# Clock_WR.net
KiCad netlist of a schematic drawn in Altium Designer
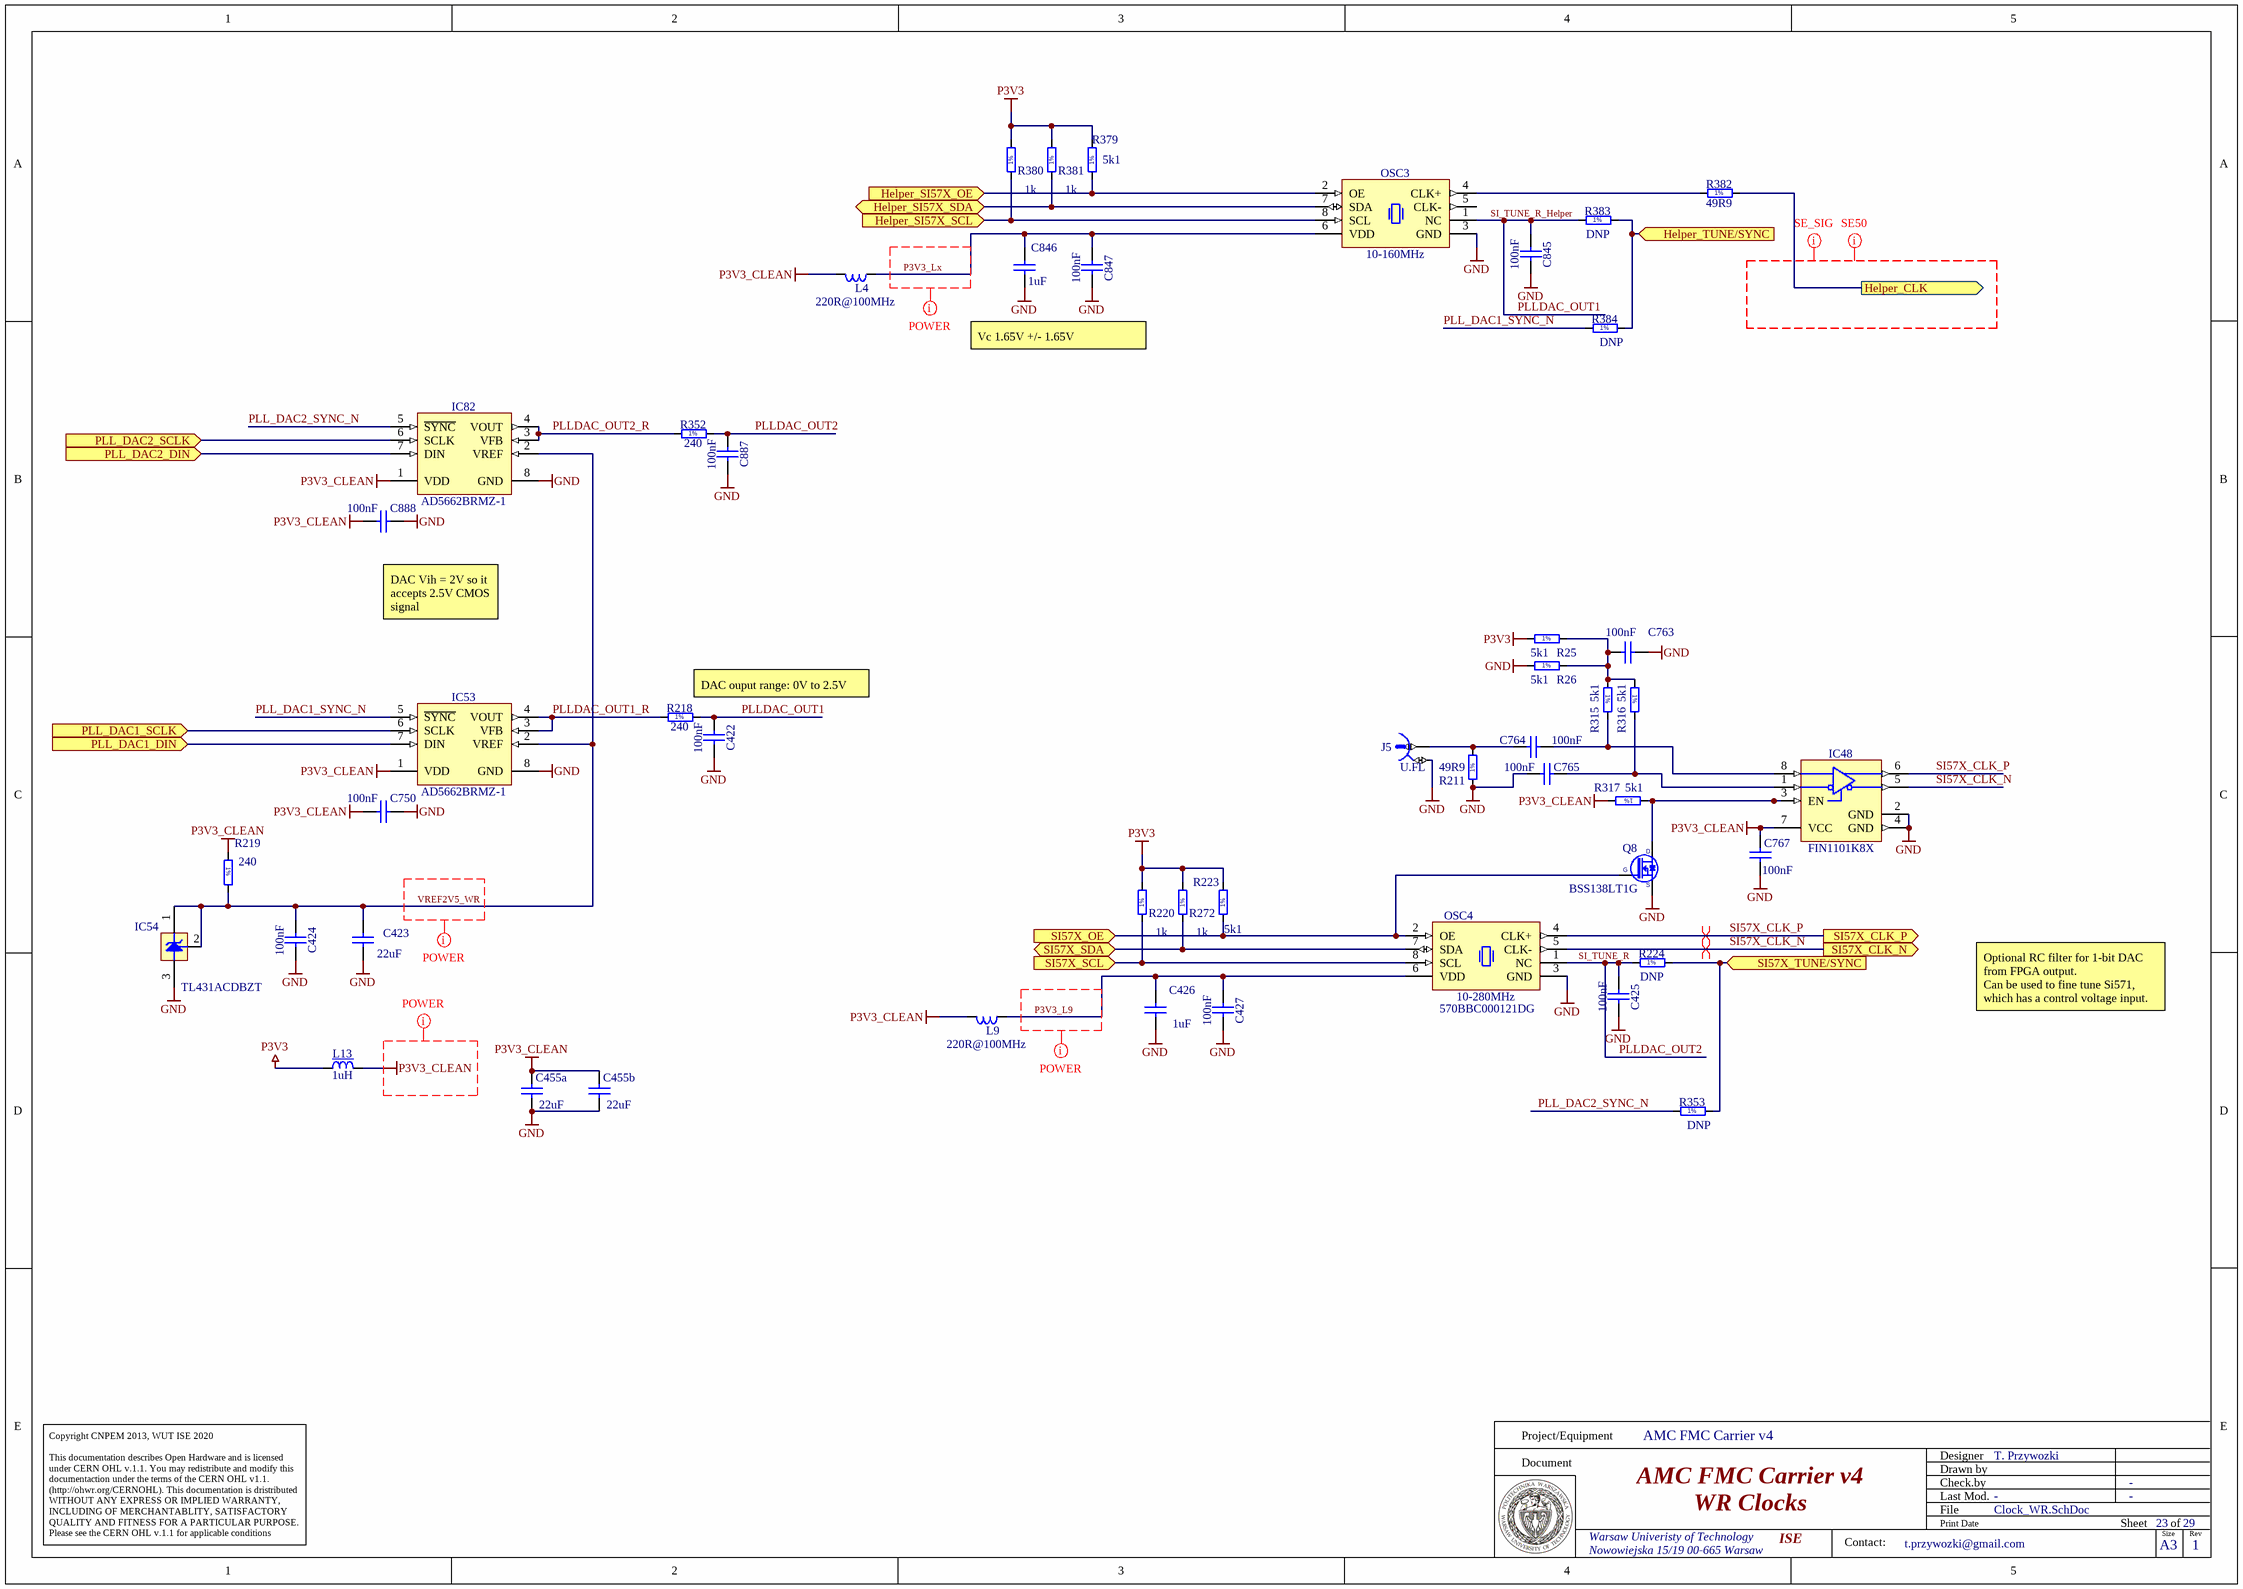
[diagram p0: Clock_WR.SchDoc]

(export (version "E")
  (design (tool "Eeschema 10.0.6"))
  (components
    (comp (ref "C422")
      (value "100nF")
      (footprint "CAPC0603X33N")
      (description "Non-polarised capacitor")
      (fields
        (field (name "PART NUMBER") "CC0201_100NF_6.3V_10%_X5R")
        (field (name "VOLTAGE") "6.3V")
        (field (name "AUTHOR") "CERN DEM JLC")
      )
      (libsource (lib "Capacitors") (part "Capacitor - non polarized"))
    )
    (comp (ref "C423")
      (value "22uF")
      (footprint "CAPC3216X180N")
      (description "Non-polarised capacitor")
      (fields
        (field (name "PART NUMBER") "CC1206_22UF_10V_10%_X7R")
        (field (name "VOLTAGE") "10V")
        (field (name "AUTHOR") "CERN DEM JLC")
      )
      (libsource (lib "Capacitors") (part "Capacitor - non polarized"))
    )
    (comp (ref "C424")
      (value "100nF")
      (footprint "CAPC0603X33N")
      (description "Non-polarised capacitor")
      (fields
        (field (name "PART NUMBER") "CC0201_100NF_6.3V_10%_X5R")
        (field (name "VOLTAGE") "6.3V")
        (field (name "AUTHOR") "CERN DEM JLC")
      )
      (libsource (lib "Capacitors") (part "Capacitor - non polarized"))
    )
    (comp (ref "C425")
      (value "100nF")
      (footprint "CAPC0603X33N")
      (description "Non-polarised capacitor")
      (fields
        (field (name "PART NUMBER") "CC0201_100NF_6.3V_10%_X5R")
        (field (name "VOLTAGE") "6.3V")
        (field (name "AUTHOR") "CERN DEM JLC")
      )
      (libsource (lib "Capacitors") (part "Capacitor - non polarized"))
    )
    (comp (ref "C426")
      (value "1uF")
      (footprint "CAPC1608X87N")
      (description "Non-polarised capacitor")
      (fields
        (field (name "PART NUMBER") "CC0603_1UF_16V_10%_X7R")
        (field (name "VOLTAGE") "16V")
        (field (name "AUTHOR") "CERN DEM JLC")
      )
      (libsource (lib "Capacitors") (part "Capacitor - non polarized"))
    )
    (comp (ref "C427")
      (value "100nF")
      (footprint "CAPC0603X33N")
      (description "Non-polarised capacitor")
      (fields
        (field (name "PART NUMBER") "CC0201_100NF_6.3V_10%_X5R")
        (field (name "VOLTAGE") "6.3V")
        (field (name "AUTHOR") "CERN DEM JLC")
      )
      (libsource (lib "Capacitors") (part "Capacitor - non polarized"))
    )
    (comp (ref "C455a")
      (value "22uF")
      (footprint "CAPC3216X180N")
      (description "Non-polarised capacitor")
      (fields
        (field (name "PART NUMBER") "CC1206_22UF_10V_10%_X7R")
        (field (name "VOLTAGE") "10V")
        (field (name "AUTHOR") "CERN DEM JLC")
      )
      (libsource (lib "Capacitors") (part "Capacitor - non polarized"))
    )
    (comp (ref "C455b")
      (value "22uF")
      (footprint "CAPC3216X180N")
      (description "Non-polarised capacitor")
      (fields
        (field (name "PART NUMBER") "CC1206_22UF_10V_10%_X7R")
        (field (name "VOLTAGE") "10V")
        (field (name "AUTHOR") "CERN DEM JLC")
      )
      (libsource (lib "Capacitors") (part "Capacitor - non polarized"))
    )
    (comp (ref "C750")
      (value "100nF")
      (footprint "CAPC0603X33N")
      (description "Non-polarised capacitor")
      (fields
        (field (name "PART NUMBER") "CC0201_100NF_6.3V_10%_X5R")
        (field (name "VOLTAGE") "6.3V")
        (field (name "AUTHOR") "CERN DEM JLC")
      )
      (libsource (lib "Capacitors") (part "Capacitor - non polarized"))
    )
    (comp (ref "C763")
      (value "100nF")
      (footprint "CAPC0603X33N")
      (description "Non-polarised capacitor")
      (fields
        (field (name "PART NUMBER") "CC0201_100NF_6.3V_10%_X5R")
        (field (name "VOLTAGE") "6.3V")
        (field (name "AUTHOR") "CERN DEM JLC")
      )
      (libsource (lib "Capacitors") (part "Capacitor - non polarized"))
    )
    (comp (ref "C764")
      (value "100nF")
      (footprint "CAPC0603X33N")
      (description "Non-polarised capacitor")
      (fields
        (field (name "PART NUMBER") "CC0201_100NF_6.3V_10%_X5R")
        (field (name "VOLTAGE") "6.3V")
        (field (name "AUTHOR") "CERN DEM JLC")
      )
      (libsource (lib "Capacitors") (part "Capacitor - non polarized"))
    )
    (comp (ref "C765")
      (value "100nF")
      (footprint "CAPC0603X33N")
      (description "Non-polarised capacitor")
      (fields
        (field (name "PART NUMBER") "CC0201_100NF_6.3V_10%_X5R")
        (field (name "VOLTAGE") "6.3V")
        (field (name "AUTHOR") "CERN DEM JLC")
      )
      (libsource (lib "Capacitors") (part "Capacitor - non polarized"))
    )
    (comp (ref "C767")
      (value "100nF")
      (footprint "CAPC0603X33N")
      (description "Non-polarised capacitor")
      (fields
        (field (name "PART NUMBER") "CC0201_100NF_6.3V_10%_X5R")
        (field (name "VOLTAGE") "6.3V")
        (field (name "AUTHOR") "CERN DEM JLC")
      )
      (libsource (lib "Capacitors") (part "Capacitor - non polarized"))
    )
    (comp (ref "C845")
      (value "100nF")
      (footprint "CAPC0603X33N")
      (description "Non-polarised capacitor")
      (fields
        (field (name "PART NUMBER") "CC0201_100NF_6.3V_10%_X5R")
        (field (name "VOLTAGE") "6.3V")
        (field (name "AUTHOR") "CERN DEM JLC")
      )
      (libsource (lib "Capacitors") (part "Capacitor - non polarized"))
    )
    (comp (ref "C846")
      (value "1uF")
      (footprint "CAPC1608X87N")
      (description "Non-polarised capacitor")
      (fields
        (field (name "PART NUMBER") "CC0603_1UF_16V_10%_X7R")
        (field (name "VOLTAGE") "16V")
        (field (name "AUTHOR") "CERN DEM JLC")
      )
      (libsource (lib "Capacitors") (part "Capacitor - non polarized"))
    )
    (comp (ref "C847")
      (value "100nF")
      (footprint "CAPC0603X33N")
      (description "Non-polarised capacitor")
      (fields
        (field (name "PART NUMBER") "CC0201_100NF_6.3V_10%_X5R")
        (field (name "VOLTAGE") "6.3V")
        (field (name "AUTHOR") "CERN DEM JLC")
      )
      (libsource (lib "Capacitors") (part "Capacitor - non polarized"))
    )
    (comp (ref "C887")
      (value "100nF")
      (footprint "CAPC0603X33N")
      (description "Non-polarised capacitor")
      (fields
        (field (name "PART NUMBER") "CC0201_100NF_6.3V_10%_X5R")
        (field (name "VOLTAGE") "6.3V")
        (field (name "AUTHOR") "CERN DEM JLC")
      )
      (libsource (lib "Capacitors") (part "Capacitor - non polarized"))
    )
    (comp (ref "C888")
      (value "100nF")
      (footprint "CAPC0603X33N")
      (description "Non-polarised capacitor")
      (fields
        (field (name "PART NUMBER") "CC0201_100NF_6.3V_10%_X5R")
        (field (name "VOLTAGE") "6.3V")
        (field (name "AUTHOR") "CERN DEM JLC")
      )
      (libsource (lib "Capacitors") (part "Capacitor - non polarized"))
    )
    (comp (ref "IC48")
      (value "FIN1101K8X")
      (footprint "SOP50P310X90-8N")
      (description "LVDS Single Port High Speed Repeater")
      (fields (field (name "MANUFACTURER") "FAIRCHILD SEMICONDUCTOR") (field (name "AUTHOR") "CERN DEM JLC"))
      (libsource (lib "ICs And Semiconductors") (part "FIN1101K8X"))
    )
    (comp (ref "IC53")
      (value "AD5662BRMZ-1")
      (footprint "SOP65P490X110-8N")
      (description "2.7V to 5.5V, 250uA, Rail-to-Rail Output 16-Bit nanoDAC")
      (fields (field (name "MANUFACTURER") "ANALOG DEVICES") (field (name "AUTHOR") "CERN DEM JLC"))
      (libsource (lib "ICs And Semiconductors") (part "AD5662"))
    )
    (comp (ref "IC54")
      (value "TL431ACDBZT")
      (footprint "SOT95P237X112-3N")
      (description "Precision Reference 1=Cathode 2=Adj 3=Anode")
      (fields (field (name "MANUFACTURER") "TEXAS INSTRUMENTS") (field (name "AUTHOR") "CERN DEM JLC"))
      (libsource (lib "ICs And Semiconductors") (part "VREF 1C-2ADJ-3A"))
    )
    (comp (ref "IC82")
      (value "AD5662BRMZ-1")
      (footprint "SOP65P490X110-8N")
      (description "2.7V to 5.5V, 250uA, Rail-to-Rail Output 16-Bit nanoDAC")
      (fields (field (name "MANUFACTURER") "ANALOG DEVICES") (field (name "AUTHOR") "CERN DEM JLC"))
      (libsource (lib "ICs And Semiconductors") (part "AD5662"))
    )
    (comp (ref "J5")
      (value "U.FL")
      (footprint "HIROSE_U.FL-R-SMT-1(10)")
      (fields
        (field (name "PART NUMBER") "HIROSE_U.FL-R-SMT-1(10)")
        (field (name "MANUFACTURER") "HIROSE (HRS)")
        (field (name "MANUFACTURER PART NUMBER") "U.FL-R-SMT-1(10)")
        (field (name "AUTHOR") "CERN DEM JLC")
      )
      (libsource (lib "Connectors") (part "Coax_1Male_1Shield"))
    )
    (comp (ref "L4")
      (value "220R@100MHz")
      (footprint "INDC2012X105N")
      (description "Inductor")
      (fields
        (field (name "PART NUMBER") "IND0805_MURATA_BLM21PG221SN1D")
        (field (name "POWER") "2A")
        (field (name "AUTHOR") "CERN DEM JLC")
      )
      (libsource (lib "Inductors & Transformers") (part "Inductor"))
    )
    (comp (ref "L9")
      (value "220R@100MHz")
      (footprint "INDC2012X105N")
      (description "Inductor")
      (fields
        (field (name "PART NUMBER") "IND0805_MURATA_BLM21PG221SN1D")
        (field (name "POWER") "2A")
        (field (name "AUTHOR") "CERN DEM JLC")
      )
      (libsource (lib "Inductors & Transformers") (part "Inductor"))
    )
    (comp (ref "L13")
      (value "1uH")
      (footprint "IND_PANASONIC_ELLVGG")
      (description "Inductor With Core")
      (fields
        (field (name "PART NUMBER") "IND_1UH_30%_PANASONIC_ELLVGG1R0N")
        (field (name "POWER") "1.8A")
        (field (name "AUTHOR") "CERN DEM JLC")
      )
      (libsource (lib "Inductors & Transformers") (part "Inductor With Magnetic core"))
    )
    (comp (ref "OSC3")
      (value "10-160MHz")
      (footprint "OSC_SILICON-LAB_SI570")
      (description "Any-Rate I2C Programmable XO Oscillator Si570 Serie")
      (fields
        (field (name "PART NUMBER") "OSC_10-160MHZ_SILICON-LAB_Si570CAC000121DG")
        (field (name "MANUFACTURER") "SILICON LABS")
        (field (name "AUTHOR") "CERN DEM JMW")
      )
      (libsource (lib "ICs And Semiconductors") (part "Oscillator SILICON-LAB_Si570"))
    )
    (comp (ref "OSC4")
      (value "10-280MHz")
      (footprint "OSC_SILICON-LAB_SI570")
      (description "Any-Rate I2C Programmable XO Oscillator Si570 Serie")
      (fields
        (field (name "PART NUMBER") "OSC_10-280MHZ_SILICON-LAB_Si570BBC000121DG")
        (field (name "MANUFACTURER") "SILICON LABS")
        (field (name "MANUFACTURER PART NUMBER") "570BBC000121DG")
        (field (name "AUTHOR") "CERN DEM JLC")
      )
      (libsource (lib "ICs And Semiconductors") (part "Oscillator SILICON-LAB_Si570"))
    )
    (comp (ref "Q8")
      (value "BSS138LT1G")
      (footprint "SOT95P240X110-3N")
      (description "N-CHANNEL MOSFET WITH DIODE")
      (fields (field (name "MANUFACTURER") "ON SEMICONDUCTOR") (field (name "AUTHOR") "CERN DEM JLC"))
      (libsource (lib "ICs And Semiconductors") (part "N-MOSFET-D 1G 2S 3D"))
    )
    (comp (ref "R25")
      (value "5k1")
      (footprint "RESC1608X55N")
      (description "Resistor - 1%")
      (fields
        (field (name "PART NUMBER") "R0603_5K1_1%_0.1W_100PPM")
        (field (name "POWER") "0.1W")
        (field (name "AUTHOR") "CERN DEM JLC")
      )
      (libsource (lib "Resistors") (part "Resistor - 1%"))
    )
    (comp (ref "R26")
      (value "5k1")
      (footprint "RESC1608X55N")
      (description "Resistor - 1%")
      (fields
        (field (name "PART NUMBER") "R0603_5K1_1%_0.1W_100PPM")
        (field (name "POWER") "0.1W")
        (field (name "AUTHOR") "CERN DEM JLC")
      )
      (libsource (lib "Resistors") (part "Resistor - 1%"))
    )
    (comp (ref "R211")
      (value "49R9")
      (footprint "RESC1005X40N")
      (description "Resistor - 1%")
      (fields
        (field (name "PART NUMBER") "R0402_49R9_1%_0.0625W_100PPM")
        (field (name "POWER") "0.0625W")
        (field (name "AUTHOR") "CERN DEM JLC")
      )
      (libsource (lib "Resistors") (part "Resistor - 1%"))
    )
    (comp (ref "R218")
      (value "240")
      (footprint "RESC1005X40N")
      (description "Resistor - 1%")
      (fields
        (field (name "PART NUMBER") "R0402_240R_1%_0.0625W_100PPM")
        (field (name "POWER") "0.0625W")
        (field (name "AUTHOR") "CERN DEM JLC")
      )
      (libsource (lib "Resistors") (part "Resistor - 1%"))
    )
    (comp (ref "R219")
      (value "240")
      (footprint "RESC1005X40N")
      (description "Resistor - 1%")
      (fields
        (field (name "PART NUMBER") "R0402_240R_1%_0.0625W_100PPM")
        (field (name "POWER") "0.0625W")
        (field (name "AUTHOR") "CERN DEM JLC")
      )
      (libsource (lib "Resistors") (part "Resistor - 1%"))
    )
    (comp (ref "R220")
      (value "1k")
      (footprint "RESC1005X40N")
      (description "Resistor - 1%")
      (fields
        (field (name "PART NUMBER") "R0402_1K_1%_0.0625W_100PPM")
        (field (name "POWER") "0.0625W")
        (field (name "AUTHOR") "CERN DEM JLC")
      )
      (libsource (lib "Resistors") (part "Resistor - 1%"))
    )
    (comp (ref "R223")
      (value "5k1")
      (footprint "RESC1608X55N")
      (description "Resistor - 1%")
      (fields
        (field (name "PART NUMBER") "R0603_5K1_1%_0.1W_100PPM")
        (field (name "POWER") "0.1W")
        (field (name "AUTHOR") "CERN DEM JLC")
      )
      (libsource (lib "Resistors") (part "Resistor - 1%"))
    )
    (comp (ref "R224")
      (value "DNP")
      (footprint "RESC1005X40N")
      (description "Resistor - 1%")
      (fields
        (field (name "PART NUMBER") "R0402_100R_1%_0.0625W_100PPM")
        (field (name "POWER") "0.0625W")
        (field (name "AUTHOR") "CERN DEM JLC")
      )
      (libsource (lib "Resistors") (part "Resistor - 1%"))
    )
    (comp (ref "R272")
      (value "1k")
      (footprint "RESC1005X40N")
      (description "Resistor - 1%")
      (fields
        (field (name "PART NUMBER") "R0402_1K_1%_0.0625W_100PPM")
        (field (name "POWER") "0.0625W")
        (field (name "AUTHOR") "CERN DEM JLC")
      )
      (libsource (lib "Resistors") (part "Resistor - 1%"))
    )
    (comp (ref "R315")
      (value "5k1")
      (footprint "RESC1608X55N")
      (description "Resistor - 1%")
      (fields
        (field (name "PART NUMBER") "R0603_5K1_1%_0.1W_100PPM")
        (field (name "POWER") "0.1W")
        (field (name "AUTHOR") "CERN DEM JLC")
      )
      (libsource (lib "Resistors") (part "Resistor - 1%"))
    )
    (comp (ref "R316")
      (value "5k1")
      (footprint "RESC1608X55N")
      (description "Resistor - 1%")
      (fields
        (field (name "PART NUMBER") "R0603_5K1_1%_0.1W_100PPM")
        (field (name "POWER") "0.1W")
        (field (name "AUTHOR") "CERN DEM JLC")
      )
      (libsource (lib "Resistors") (part "Resistor - 1%"))
    )
    (comp (ref "R317")
      (value "5k1")
      (footprint "RESC1608X55N")
      (description "Resistor - 1%")
      (fields
        (field (name "PART NUMBER") "R0603_5K1_1%_0.1W_100PPM")
        (field (name "POWER") "0.1W")
        (field (name "AUTHOR") "CERN DEM JLC")
      )
      (libsource (lib "Resistors") (part "Resistor - 1%"))
    )
    (comp (ref "R352")
      (value "240")
      (footprint "RESC1005X40N")
      (description "Resistor - 1%")
      (fields
        (field (name "PART NUMBER") "R0402_240R_1%_0.0625W_100PPM")
        (field (name "POWER") "0.0625W")
        (field (name "AUTHOR") "CERN DEM JLC")
      )
      (libsource (lib "Resistors") (part "Resistor - 1%"))
    )
    (comp (ref "R353")
      (value "DNP")
      (footprint "RESC1005X40N")
      (description "Resistor - 1%")
      (fields
        (field (name "PART NUMBER") "R0402_100R_1%_0.0625W_100PPM")
        (field (name "POWER") "0.0625W")
        (field (name "AUTHOR") "CERN DEM JLC")
      )
      (libsource (lib "Resistors") (part "Resistor - 1%"))
    )
    (comp (ref "R379")
      (value "5k1")
      (footprint "RESC1608X55N")
      (description "Resistor - 1%")
      (fields
        (field (name "PART NUMBER") "R0603_5K1_1%_0.1W_100PPM")
        (field (name "POWER") "0.1W")
        (field (name "AUTHOR") "CERN DEM JLC")
      )
      (libsource (lib "Resistors") (part "Resistor - 1%"))
    )
    (comp (ref "R380")
      (value "1k")
      (footprint "RESC1005X40N")
      (description "Resistor - 1%")
      (fields
        (field (name "PART NUMBER") "R0402_1K_1%_0.0625W_100PPM")
        (field (name "POWER") "0.0625W")
        (field (name "AUTHOR") "CERN DEM JLC")
      )
      (libsource (lib "Resistors") (part "Resistor - 1%"))
    )
    (comp (ref "R381")
      (value "1k")
      (footprint "RESC1005X40N")
      (description "Resistor - 1%")
      (fields
        (field (name "PART NUMBER") "R0402_1K_1%_0.0625W_100PPM")
        (field (name "POWER") "0.0625W")
        (field (name "AUTHOR") "CERN DEM JLC")
      )
      (libsource (lib "Resistors") (part "Resistor - 1%"))
    )
    (comp (ref "R382")
      (value "49R9")
      (footprint "RESC1005X40N")
      (description "Resistor - 1%")
      (fields
        (field (name "PART NUMBER") "R0402_49R9_1%_0.0625W_100PPM")
        (field (name "POWER") "0.0625W")
        (field (name "AUTHOR") "CERN DEM JLC")
      )
      (libsource (lib "Resistors") (part "Resistor - 1%"))
    )
    (comp (ref "R383")
      (value "DNP")
      (footprint "RESC1005X40N")
      (description "Resistor - 1%")
      (fields
        (field (name "PART NUMBER") "R0402_100R_1%_0.0625W_100PPM")
        (field (name "POWER") "0.0625W")
        (field (name "AUTHOR") "CERN DEM JLC")
      )
      (libsource (lib "Resistors") (part "Resistor - 1%"))
    )
    (comp (ref "R384")
      (value "DNP")
      (footprint "RESC1005X40N")
      (description "Resistor - 1%")
      (fields
        (field (name "PART NUMBER") "R0402_100R_1%_0.0625W_100PPM")
        (field (name "POWER") "0.0625W")
        (field (name "AUTHOR") "CERN DEM JLC")
      )
      (libsource (lib "Resistors") (part "Resistor - 1%"))
    )
  )
  (nets
    (net (code "1") (name "/Helper_CLK") (class "Default")
      (node (ref "R382") (pin "2") (pinfunction "2_2") (pintype "passive"))
    )
    (net (code "2") (name "/Helper_SI57X_OE") (class "Default")
      (node (ref "OSC3") (pin "2") (pinfunction "OE_2") (pintype "input"))
      (node (ref "R379") (pin "1") (pinfunction "1_1") (pintype "passive"))
    )
    (net (code "3") (name "/Helper_SI57X_SCL") (class "Default")
      (node (ref "OSC3") (pin "8") (pinfunction "SCL_8") (pintype "input"))
      (node (ref "R380") (pin "1") (pinfunction "1_1") (pintype "passive"))
    )
    (net (code "4") (name "/Helper_SI57X_SDA") (class "Default")
      (node (ref "OSC3") (pin "7") (pinfunction "SDA_7") (pintype "bidirectional"))
      (node (ref "R381") (pin "1") (pinfunction "1_1") (pintype "passive"))
    )
    (net (code "5") (name "/Helper_TUNE{slash}SYNC") (class "Default")
      (node (ref "R383") (pin "2") (pinfunction "2_2") (pintype "passive"))
      (node (ref "R384") (pin "2") (pinfunction "2_2") (pintype "passive"))
    )
    (net (code "6") (name "/P3V3_L9") (class "Default")
      (node (ref "C426") (pin "2") (pinfunction "2_2") (pintype "passive"))
      (node (ref "C427") (pin "1") (pinfunction "1_1") (pintype "passive"))
      (node (ref "L9") (pin "1") (pinfunction "1_1") (pintype "passive"))
      (node (ref "OSC4") (pin "6") (pinfunction "VDD_6") (pintype "power_in"))
    )
    (net (code "7") (name "/P3V3_Lx") (class "Default")
      (node (ref "C846") (pin "2") (pinfunction "2_2") (pintype "passive"))
      (node (ref "C847") (pin "1") (pinfunction "1_1") (pintype "passive"))
      (node (ref "L4") (pin "1") (pinfunction "1_1") (pintype "passive"))
      (node (ref "OSC3") (pin "6") (pinfunction "VDD_6") (pintype "power_in"))
    )
    (net (code "8") (name "/PLLDAC_OUT1") (class "Default")
      (node (ref "C422") (pin "1") (pinfunction "1_1") (pintype "passive"))
      (node (ref "C845") (pin "1") (pinfunction "1_1") (pintype "passive"))
      (node (ref "OSC3") (pin "1") (pinfunction "NC_1") (pintype "passive"))
      (node (ref "R218") (pin "2") (pinfunction "2_2") (pintype "passive"))
      (node (ref "R383") (pin "1") (pinfunction "1_1") (pintype "passive"))
    )
    (net (code "9") (name "/PLLDAC_OUT1_R") (class "Default")
      (node (ref "IC53") (pin "3") (pinfunction "VFB_3") (pintype "input"))
      (node (ref "IC53") (pin "4") (pinfunction "VOUT_4") (pintype "output"))
      (node (ref "R218") (pin "1") (pinfunction "1_1") (pintype "passive"))
    )
    (net (code "10") (name "/PLLDAC_OUT2") (class "Default")
      (node (ref "C425") (pin "1") (pinfunction "1_1") (pintype "passive"))
      (node (ref "C887") (pin "1") (pinfunction "1_1") (pintype "passive"))
      (node (ref "OSC4") (pin "1") (pinfunction "NC_1") (pintype "passive"))
      (node (ref "R224") (pin "1") (pinfunction "1_1") (pintype "passive"))
      (node (ref "R352") (pin "2") (pinfunction "2_2") (pintype "passive"))
    )
    (net (code "11") (name "/PLLDAC_OUT2_R") (class "Default")
      (node (ref "IC82") (pin "3") (pinfunction "VFB_3") (pintype "input"))
      (node (ref "IC82") (pin "4") (pinfunction "VOUT_4") (pintype "output"))
      (node (ref "R352") (pin "1") (pinfunction "1_1") (pintype "passive"))
    )
    (net (code "12") (name "/PLL_DAC1_DIN") (class "Default")
      (node (ref "IC53") (pin "7") (pinfunction "DIN_7") (pintype "input"))
    )
    (net (code "13") (name "/PLL_DAC1_SCLK") (class "Default")
      (node (ref "IC53") (pin "6") (pinfunction "SCLK_6") (pintype "input"))
    )
    (net (code "14") (name "/PLL_DAC1_SYNC_N") (class "Default")
      (node (ref "IC53") (pin "5") (pinfunction "~{SYNC}_5") (pintype "input"))
      (node (ref "R384") (pin "1") (pinfunction "1_1") (pintype "passive"))
    )
    (net (code "15") (name "/PLL_DAC2_DIN") (class "Default")
      (node (ref "IC82") (pin "7") (pinfunction "DIN_7") (pintype "input"))
    )
    (net (code "16") (name "/PLL_DAC2_SCLK") (class "Default")
      (node (ref "IC82") (pin "6") (pinfunction "SCLK_6") (pintype "input"))
    )
    (net (code "17") (name "/PLL_DAC2_SYNC_N") (class "Default")
      (node (ref "IC82") (pin "5") (pinfunction "~{SYNC}_5") (pintype "input"))
      (node (ref "R353") (pin "1") (pinfunction "1_1") (pintype "passive"))
    )
    (net (code "18") (name "/SI57X_CLK_N") (class "Default")
      (node (ref "IC48") (pin "5") (pinfunction "DOUT-_5") (pintype "output"))
      (node (ref "OSC4") (pin "5") (pinfunction "CLK-_5") (pintype "output"))
    )
    (net (code "19") (name "/SI57X_CLK_P") (class "Default")
      (node (ref "IC48") (pin "6") (pinfunction "DOUT+_6") (pintype "output"))
      (node (ref "OSC4") (pin "4") (pinfunction "CLK+_4") (pintype "output"))
    )
    (net (code "20") (name "/SI57X_OE") (class "Default")
      (node (ref "OSC4") (pin "2") (pinfunction "OE_2") (pintype "input"))
      (node (ref "Q8") (pin "1") (pinfunction "G_1") (pintype "passive"))
      (node (ref "R223") (pin "1") (pinfunction "1_1") (pintype "passive"))
    )
    (net (code "21") (name "/SI57X_SCL") (class "Default")
      (node (ref "OSC4") (pin "8") (pinfunction "SCL_8") (pintype "input"))
      (node (ref "R220") (pin "1") (pinfunction "1_1") (pintype "passive"))
    )
    (net (code "22") (name "/SI57X_SDA") (class "Default")
      (node (ref "OSC4") (pin "7") (pinfunction "SDA_7") (pintype "bidirectional"))
      (node (ref "R272") (pin "1") (pinfunction "1_1") (pintype "passive"))
    )
    (net (code "23") (name "/SI57X_TUNE{slash}SYNC") (class "Default")
      (node (ref "R224") (pin "2") (pinfunction "2_2") (pintype "passive"))
      (node (ref "R353") (pin "2") (pinfunction "2_2") (pintype "passive"))
    )
    (net (code "24") (name "/VREF2V5_WR") (class "Default")
      (node (ref "C423") (pin "2") (pinfunction "2_2") (pintype "passive"))
      (node (ref "C424") (pin "1") (pinfunction "1_1") (pintype "passive"))
      (node (ref "IC53") (pin "2") (pinfunction "VREF_2") (pintype "input"))
      (node (ref "IC54") (pin "1") (pinfunction "C_1") (pintype "passive"))
      (node (ref "IC54") (pin "2") (pinfunction "Adj_2") (pintype "passive"))
      (node (ref "IC82") (pin "2") (pinfunction "VREF_2") (pintype "input"))
      (node (ref "R219") (pin "2") (pinfunction "2_2") (pintype "passive"))
    )
    (net (code "25") (name "GND") (class "Default")
      (node (ref "C422") (pin "2") (pinfunction "2_2") (pintype "passive"))
      (node (ref "C423") (pin "1") (pinfunction "1_1") (pintype "passive"))
      (node (ref "C424") (pin "2") (pinfunction "2_2") (pintype "passive"))
      (node (ref "C425") (pin "2") (pinfunction "2_2") (pintype "passive"))
      (node (ref "C426") (pin "1") (pinfunction "1_1") (pintype "passive"))
      (node (ref "C427") (pin "2") (pinfunction "2_2") (pintype "passive"))
      (node (ref "C455a") (pin "1") (pinfunction "1_1") (pintype "passive"))
      (node (ref "C455b") (pin "1") (pinfunction "1_1") (pintype "passive"))
      (node (ref "C750") (pin "2") (pinfunction "2_2") (pintype "passive"))
      (node (ref "C763") (pin "2") (pinfunction "2_2") (pintype "passive"))
      (node (ref "C765") (pin "1") (pinfunction "1_1") (pintype "passive"))
      (node (ref "C767") (pin "2") (pinfunction "2_2") (pintype "passive"))
      (node (ref "C845") (pin "2") (pinfunction "2_2") (pintype "passive"))
      (node (ref "C846") (pin "1") (pinfunction "1_1") (pintype "passive"))
      (node (ref "C847") (pin "2") (pinfunction "2_2") (pintype "passive"))
      (node (ref "C887") (pin "2") (pinfunction "2_2") (pintype "passive"))
      (node (ref "C888") (pin "2") (pinfunction "2_2") (pintype "passive"))
      (node (ref "IC48") (pin "2") (pinfunction "GND_2") (pintype "power_in"))
      (node (ref "IC48") (pin "4") (pinfunction "GND_4") (pintype "output"))
      (node (ref "IC53") (pin "8") (pinfunction "GND_8") (pintype "power_in"))
      (node (ref "IC54") (pin "3") (pinfunction "A_3") (pintype "passive"))
      (node (ref "IC82") (pin "8") (pinfunction "GND_8") (pintype "power_in"))
      (node (ref "J5") (pin "2") (pinfunction "2_2") (pintype "bidirectional"))
      (node (ref "OSC3") (pin "3") (pinfunction "GND_3") (pintype "power_in"))
      (node (ref "OSC4") (pin "3") (pinfunction "GND_3") (pintype "power_in"))
      (node (ref "Q8") (pin "2") (pinfunction "S_2") (pintype "passive"))
      (node (ref "R211") (pin "1") (pinfunction "1_1") (pintype "passive"))
      (node (ref "R26") (pin "1") (pinfunction "1_1") (pintype "passive"))
    )
    (net (code "26") (name "Net-(C763-Pad1)") (class "Default")
      (node (ref "C763") (pin "1") (pinfunction "1_1") (pintype "passive"))
      (node (ref "R25") (pin "2") (pinfunction "2_2") (pintype "passive"))
      (node (ref "R26") (pin "2") (pinfunction "2_2") (pintype "passive"))
      (node (ref "R315") (pin "1") (pinfunction "1_1") (pintype "passive"))
      (node (ref "R316") (pin "1") (pinfunction "1_1") (pintype "passive"))
    )
    (net (code "27") (name "Net-(C764-Pad2)") (class "Default")
      (node (ref "C764") (pin "2") (pinfunction "2_2") (pintype "passive"))
      (node (ref "J5") (pin "1") (pinfunction "1_1") (pintype "bidirectional"))
      (node (ref "R211") (pin "2") (pinfunction "2_2") (pintype "passive"))
    )
    (net (code "28") (name "Net-(IC48-EN)") (class "Default")
      (node (ref "IC48") (pin "3") (pinfunction "EN_3") (pintype "input"))
      (node (ref "Q8") (pin "3") (pinfunction "D_3") (pintype "passive"))
      (node (ref "R317") (pin "1") (pinfunction "1_1") (pintype "passive"))
    )
    (net (code "29") (name "Net-(IC48-RIN+)") (class "Default")
      (node (ref "C764") (pin "1") (pinfunction "1_1") (pintype "passive"))
      (node (ref "IC48") (pin "8") (pinfunction "RIN+_8") (pintype "input"))
      (node (ref "R315") (pin "2") (pinfunction "2_2") (pintype "passive"))
    )
    (net (code "30") (name "Net-(IC48-RIN-)") (class "Default")
      (node (ref "C765") (pin "2") (pinfunction "2_2") (pintype "passive"))
      (node (ref "IC48") (pin "1") (pinfunction "RIN-_1") (pintype "input"))
      (node (ref "R316") (pin "2") (pinfunction "2_2") (pintype "passive"))
    )
    (net (code "31") (name "Net-(OSC3-CLK+)") (class "Default")
      (node (ref "OSC3") (pin "4") (pinfunction "CLK+_4") (pintype "output"))
      (node (ref "R382") (pin "1") (pinfunction "1_1") (pintype "passive"))
    )
    (net (code "32") (name "P3V3") (class "Default")
      (node (ref "L13") (pin "1") (pinfunction "1_1") (pintype "passive"))
      (node (ref "R220") (pin "2") (pinfunction "2_2") (pintype "passive"))
      (node (ref "R223") (pin "2") (pinfunction "2_2") (pintype "passive"))
      (node (ref "R25") (pin "1") (pinfunction "1_1") (pintype "passive"))
      (node (ref "R272") (pin "2") (pinfunction "2_2") (pintype "passive"))
      (node (ref "R379") (pin "2") (pinfunction "2_2") (pintype "passive"))
      (node (ref "R380") (pin "2") (pinfunction "2_2") (pintype "passive"))
      (node (ref "R381") (pin "2") (pinfunction "2_2") (pintype "passive"))
    )
    (net (code "33") (name "P3V3_CLEAN") (class "Default")
      (node (ref "C455a") (pin "2") (pinfunction "2_2") (pintype "passive"))
      (node (ref "C455b") (pin "2") (pinfunction "2_2") (pintype "passive"))
      (node (ref "C750") (pin "1") (pinfunction "1_1") (pintype "passive"))
      (node (ref "C767") (pin "1") (pinfunction "1_1") (pintype "passive"))
      (node (ref "C888") (pin "1") (pinfunction "1_1") (pintype "passive"))
      (node (ref "IC48") (pin "7") (pinfunction "VCC_7") (pintype "power_in"))
      (node (ref "IC53") (pin "1") (pinfunction "VDD_1") (pintype "power_in"))
      (node (ref "IC82") (pin "1") (pinfunction "VDD_1") (pintype "power_in"))
      (node (ref "L13") (pin "2") (pinfunction "2_2") (pintype "passive"))
      (node (ref "L4") (pin "2") (pinfunction "2_2") (pintype "passive"))
      (node (ref "L9") (pin "2") (pinfunction "2_2") (pintype "passive"))
      (node (ref "R219") (pin "1") (pinfunction "1_1") (pintype "passive"))
      (node (ref "R317") (pin "2") (pinfunction "2_2") (pintype "passive"))
    )
    (net (code "34") (name "unconnected-(OSC3-CLK--Pad5)") (class "Default")
      (node (ref "OSC3") (pin "5") (pinfunction "CLK-_5") (pintype "output"))
    )
  )
)
